# Battery_Monitor_Ard.net
KiCad netlist of a schematic drawn in EAGLE
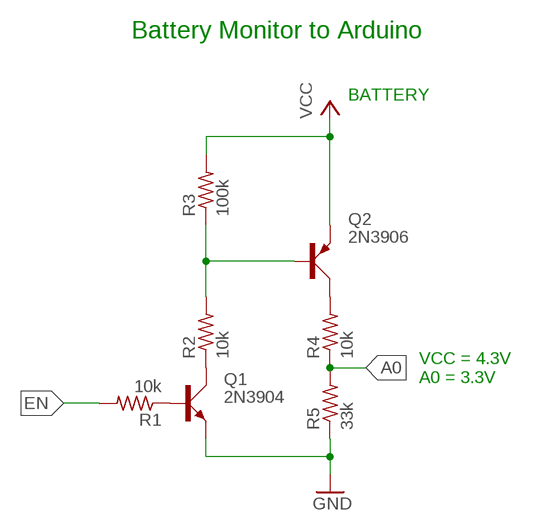
[diagram p0: schematic, sheet 1]

(export (version "E")
  (design (tool "Eeschema 10.0.6"))
  (components
    (comp (ref "Q1")
      (value "2N3904")
      (footprint "eagle-import:TO92D")
      (libsource (lib "eagle-import") (part "2N3904"))
    )
    (comp (ref "Q2")
      (value "2N3906")
      (footprint "eagle-import:TO92D")
      (libsource (lib "eagle-import") (part "2N3906"))
    )
    (comp (ref "R1")
      (value "10k")
      (footprint "eagle-import:0207_10")
      (libsource (lib "eagle-import") (part "R-US_0207/10"))
    )
    (comp (ref "R2")
      (value "10k")
      (footprint "eagle-import:0207_10")
      (libsource (lib "eagle-import") (part "R-US_0207/10"))
    )
    (comp (ref "R3")
      (value "100k")
      (footprint "eagle-import:0207_10")
      (libsource (lib "eagle-import") (part "R-US_0207/10"))
    )
    (comp (ref "R4")
      (value "10k")
      (footprint "eagle-import:0207_10")
      (libsource (lib "eagle-import") (part "R-US_0207/10"))
    )
    (comp (ref "R5")
      (value "33k")
      (footprint "eagle-import:0207_10")
      (libsource (lib "eagle-import") (part "R-US_0207/10"))
    )
  )
  (nets
    (net (code "1") (name "A0") (class "Default")
      (node (ref "R4") (pin "1") (pinfunction "1_1") (pintype "passive"))
      (node (ref "R5") (pin "2") (pinfunction "2_2") (pintype "passive"))
    )
    (net (code "2") (name "EN") (class "Default")
      (node (ref "R1") (pin "2") (pinfunction "2_2") (pintype "passive"))
    )
    (net (code "3") (name "GND") (class "Default")
      (node (ref "Q1") (pin "E") (pinfunction "E_E") (pintype "passive"))
      (node (ref "R5") (pin "1") (pinfunction "1_1") (pintype "passive"))
    )
    (net (code "4") (name "Net-(Q1-PadB)") (class "Default")
      (node (ref "Q1") (pin "B") (pinfunction "B_B") (pintype "passive"))
      (node (ref "R1") (pin "1") (pinfunction "1_1") (pintype "passive"))
    )
    (net (code "5") (name "Net-(Q1-PadC)") (class "Default")
      (node (ref "Q1") (pin "C") (pinfunction "C_C") (pintype "passive"))
      (node (ref "R2") (pin "1") (pinfunction "1_1") (pintype "passive"))
    )
    (net (code "6") (name "Net-(Q2-PadB)") (class "Default")
      (node (ref "Q2") (pin "B") (pinfunction "B_B") (pintype "passive"))
      (node (ref "R2") (pin "2") (pinfunction "2_2") (pintype "passive"))
      (node (ref "R3") (pin "1") (pinfunction "1_1") (pintype "passive"))
    )
    (net (code "7") (name "Net-(Q2-PadC)") (class "Default")
      (node (ref "Q2") (pin "C") (pinfunction "C_C") (pintype "passive"))
      (node (ref "R4") (pin "2") (pinfunction "2_2") (pintype "passive"))
    )
    (net (code "8") (name "VCC") (class "Default")
      (node (ref "Q2") (pin "E") (pinfunction "E_E") (pintype "passive"))
      (node (ref "R3") (pin "2") (pinfunction "2_2") (pintype "passive"))
    )
  )
)
